# Power.net
KiCad netlist of a schematic drawn in Altium Designer
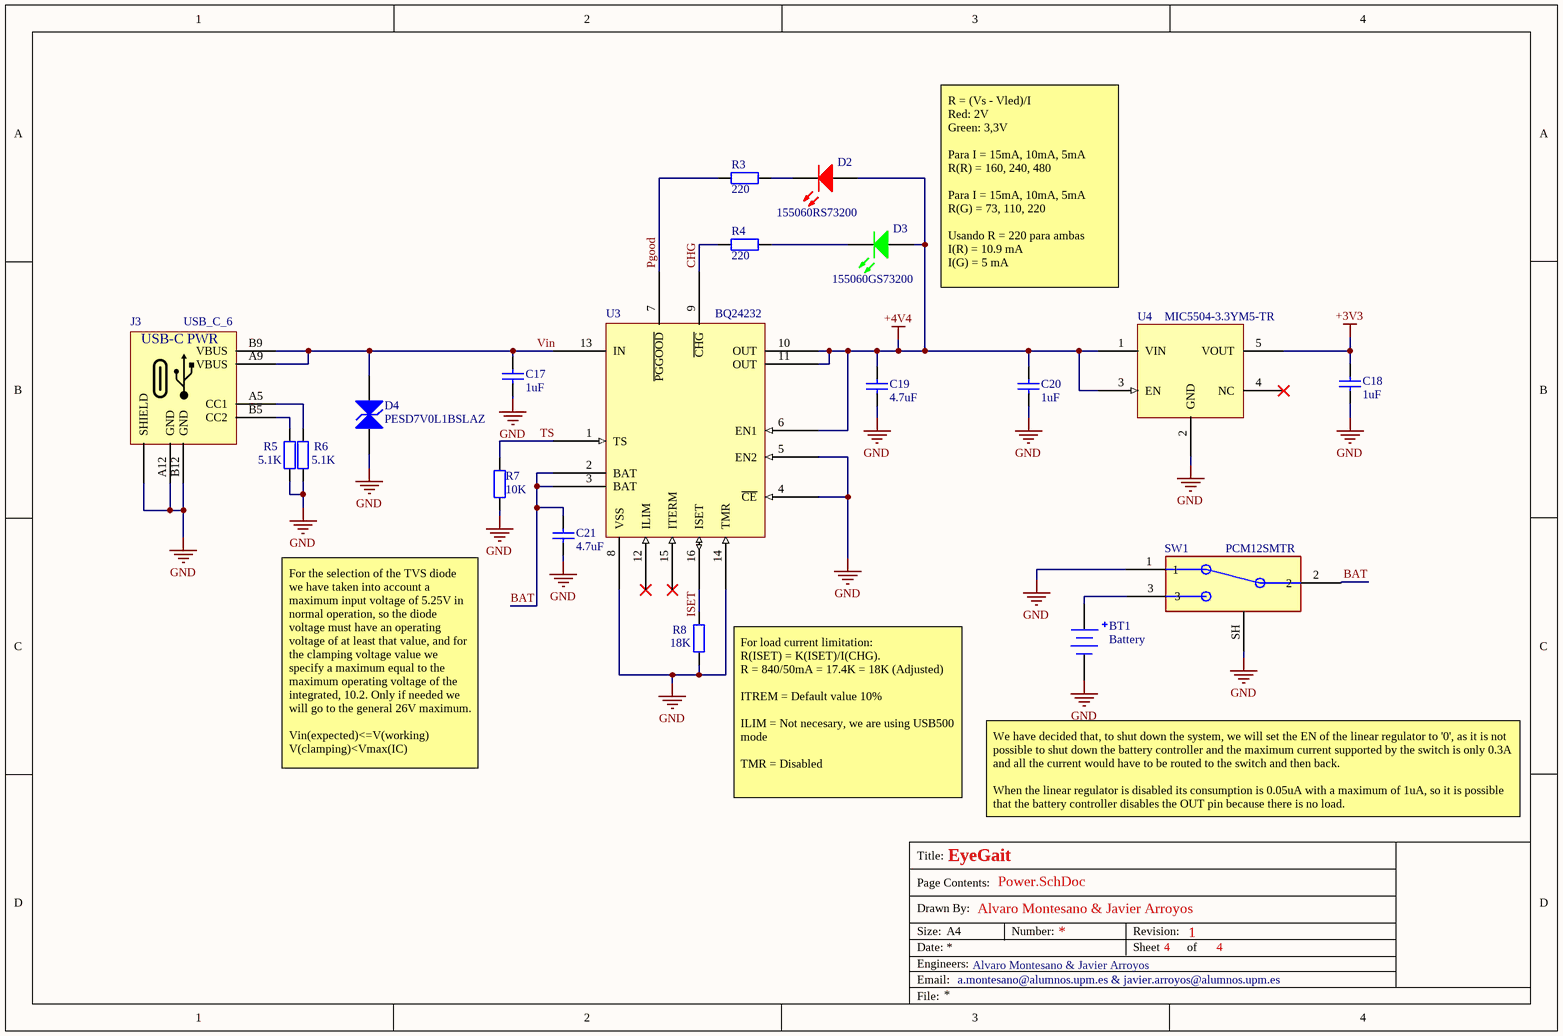
[diagram p0: Power.SchDoc]

(export (version "E")
  (design (tool "Eeschema 10.0.6"))
  (components
    (comp (ref "BT1")
      (value "Battery")
      (footprint "Hand solder wire polarity")
      (description "Multicell Battery")
      (libsource (lib "DEOP2324") (part "Battery"))
    )
    (comp (ref "C17")
      (value "1uF")
      (footprint "C0402")
      (description "Capacitor")
      (libsource (lib "DEOP2324") (part "C"))
    )
    (comp (ref "C18")
      (value "1uF")
      (footprint "C0402")
      (description "Capacitor")
      (libsource (lib "DEOP2324") (part "C"))
    )
    (comp (ref "C19")
      (value "4.7uF")
      (footprint "C0402")
      (description "Capacitor")
      (fields (field (name "VOLTAGE") ">10V"))
      (libsource (lib "DEOP2324") (part "C"))
    )
    (comp (ref "C20")
      (value "1uF")
      (footprint "C0402")
      (description "Capacitor")
      (libsource (lib "DEOP2324") (part "C"))
    )
    (comp (ref "C21")
      (value "4.7uF")
      (footprint "C0402")
      (description "Capacitor")
      (libsource (lib "DEOP2324") (part "C"))
    )
    (comp (ref "D2")
      (value "155060RS73200")
      (footprint "LED_Side_0603")
      (description "Red LED")
      (libsource (lib "DEOP2324") (part "LED_R"))
    )
    (comp (ref "D3")
      (value "155060GS73200")
      (footprint "LED_Side_0603")
      (description "Green LED")
      (libsource (lib "DEOP2324") (part "LED_G"))
    )
    (comp (ref "D4")
      (value "PESD7V0L1BSLAZ")
      (footprint "DFN1006-2/SOD882")
      (description "Zener Diode Bidirectional")
      (libsource (lib "DEOP2324") (part "D Zener_Bidirectional"))
    )
    (comp (ref "J3")
      (value "USB_C_6")
      (footprint "USB4135-GF-A")
      (description "USB-C 6 pin connector for power only. 20V/3A")
      (libsource (lib "DEOP2324") (part "USB_C_6"))
    )
    (comp (ref "R3")
      (value "220")
      (footprint "R0402")
      (description "Resistor")
      (libsource (lib "") (part "R_2"))
    )
    (comp (ref "R4")
      (value "220")
      (footprint "R0402")
      (description "Resistor")
      (libsource (lib "") (part "R_2"))
    )
    (comp (ref "R5")
      (value "5.1K")
      (footprint "R0402")
      (description "Resistor")
      (libsource (lib "DEOP2324") (part "R"))
    )
    (comp (ref "R6")
      (value "5.1K")
      (footprint "R0402")
      (description "Resistor")
      (libsource (lib "DEOP2324") (part "R"))
    )
    (comp (ref "R7")
      (value "10K")
      (footprint "R0402")
      (description "Resistor")
      (libsource (lib "") (part "R_1"))
    )
    (comp (ref "R8")
      (value "18K")
      (footprint "R0402")
      (description "Resistor")
      (libsource (lib "DEOP2324") (part "R"))
    )
    (comp (ref "SW1")
      (value "PCM12SMTR")
      (footprint "PCM12SMTR")
      (libsource (lib "DEOP2324") (part "PCM12SMTR"))
    )
    (comp (ref "U3")
      (value "BQ24232")
      (footprint "QFN50P300X300X100_HS-17N")
      (description "Power management IC. USB-Friendly Lithium-Ion Battery Charger And Power-Path Management IC")
      (libsource (lib "DEOP2324") (part "BQ24232"))
    )
    (comp (ref "U4")
      (value "MIC5504-3.3YM5-TR")
      (footprint "SOT23-5")
      (libsource (lib "DEOP2324") (part "MIC5504-3.3YM5-TR"))
    )
  )
  (nets
    (net (code "1") (name "+3V3") (class "Default")
      (node (ref "C18") (pin "1") (pinfunction "1_1") (pintype "passive"))
      (node (ref "U4") (pin "5") (pinfunction "VOUT_5") (pintype "power_in"))
    )
    (net (code "2") (name "+4V4") (class "Default")
      (node (ref "C19") (pin "1") (pinfunction "1_1") (pintype "passive"))
      (node (ref "C20") (pin "1") (pinfunction "1_1") (pintype "passive"))
      (node (ref "D2") (pin "1") (pinfunction "A_1") (pintype "passive"))
      (node (ref "D3") (pin "1") (pinfunction "A_1") (pintype "passive"))
      (node (ref "U3") (pin "10") (pinfunction "OUT_10") (pintype "power_in"))
      (node (ref "U3") (pin "11") (pinfunction "OUT_11") (pintype "power_in"))
      (node (ref "U3") (pin "6") (pinfunction "EN1_6") (pintype "input"))
      (node (ref "U4") (pin "1") (pinfunction "VIN_1") (pintype "power_in"))
      (node (ref "U4") (pin "3") (pinfunction "EN_3") (pintype "input"))
    )
    (net (code "3") (name "/BAT") (class "Default")
      (node (ref "C21") (pin "1") (pinfunction "1_1") (pintype "passive"))
      (node (ref "SW1") (pin "2") (pinfunction "2_2") (pintype "passive"))
      (node (ref "U3") (pin "2") (pinfunction "BAT_2") (pintype "power_in"))
      (node (ref "U3") (pin "3") (pinfunction "BAT_3") (pintype "power_in"))
    )
    (net (code "4") (name "/CHG") (class "Default")
      (node (ref "R4") (pin "2") (pinfunction "2_2") (pintype "passive"))
      (node (ref "U3") (pin "9") (pinfunction "~{CHG}_9") (pintype "open_collector"))
    )
    (net (code "5") (name "/ISET") (class "Default")
      (node (ref "R8") (pin "2") (pinfunction "2_2") (pintype "passive"))
      (node (ref "U3") (pin "16") (pinfunction "ISET_16") (pintype "bidirectional"))
    )
    (net (code "6") (name "/Pgood") (class "Default")
      (node (ref "R3") (pin "2") (pinfunction "2_2") (pintype "passive"))
      (node (ref "U3") (pin "7") (pinfunction "~{PGGOOD}_7") (pintype "open_collector"))
    )
    (net (code "7") (name "/TS") (class "Default")
      (node (ref "R7") (pin "1") (pinfunction "1_1") (pintype "passive"))
      (node (ref "U3") (pin "1") (pinfunction "TS_1") (pintype "input"))
    )
    (net (code "8") (name "/Vin") (class "Default")
      (node (ref "C17") (pin "1") (pinfunction "1_1") (pintype "passive"))
      (node (ref "D4") (pin "2") (pinfunction "K_2") (pintype "passive"))
      (node (ref "J3") (pin "A9") (pinfunction "VBUS_A9") (pintype "power_in"))
      (node (ref "J3") (pin "B9") (pinfunction "VBUS_B9") (pintype "power_in"))
      (node (ref "U3") (pin "13") (pinfunction "IN_13") (pintype "power_in"))
    )
    (net (code "9") (name "GND") (class "Default")
      (node (ref "BT1") (pin "2") (pinfunction "-_2") (pintype "passive"))
      (node (ref "C17") (pin "2") (pinfunction "2_2") (pintype "passive"))
      (node (ref "C18") (pin "2") (pinfunction "2_2") (pintype "passive"))
      (node (ref "C19") (pin "2") (pinfunction "2_2") (pintype "passive"))
      (node (ref "C20") (pin "2") (pinfunction "2_2") (pintype "passive"))
      (node (ref "C21") (pin "2") (pinfunction "2_2") (pintype "passive"))
      (node (ref "D4") (pin "1") (pinfunction "A_1") (pintype "passive"))
      (node (ref "J3") (pin "A12") (pinfunction "GND_A12") (pintype "power_in"))
      (node (ref "J3") (pin "B12") (pinfunction "GND_B12") (pintype "power_in"))
      (node (ref "J3") (pin "SHIELD") (pinfunction "SHIELD_SHIELD") (pintype "passive"))
      (node (ref "R5") (pin "1") (pinfunction "1_1") (pintype "passive"))
      (node (ref "R6") (pin "1") (pinfunction "1_1") (pintype "passive"))
      (node (ref "R7") (pin "2") (pinfunction "2_2") (pintype "passive"))
      (node (ref "R8") (pin "1") (pinfunction "1_1") (pintype "passive"))
      (node (ref "SW1") (pin "1") (pinfunction "1_1") (pintype "passive"))
      (node (ref "SW1") (pin "SH") (pinfunction "SH_SH") (pintype "passive"))
      (node (ref "U3") (pin "14") (pinfunction "TMR_14") (pintype "input"))
      (node (ref "U3") (pin "4") (pinfunction "~{CE}_4") (pintype "input"))
      (node (ref "U3") (pin "5") (pinfunction "EN2_5") (pintype "input"))
      (node (ref "U3") (pin "8") (pinfunction "VSS_8") (pintype "power_in"))
      (node (ref "U4") (pin "2") (pinfunction "GND_2") (pintype "power_in"))
    )
    (net (code "10") (name "Net-(BT1-+)") (class "Default")
      (node (ref "BT1") (pin "1") (pinfunction "+_1") (pintype "passive"))
      (node (ref "SW1") (pin "3") (pinfunction "3_3") (pintype "passive"))
    )
    (net (code "11") (name "Net-(D2-K)") (class "Default")
      (node (ref "D2") (pin "2") (pinfunction "K_2") (pintype "passive"))
      (node (ref "R3") (pin "1") (pinfunction "1_1") (pintype "passive"))
    )
    (net (code "12") (name "Net-(D3-K)") (class "Default")
      (node (ref "D3") (pin "2") (pinfunction "K_2") (pintype "passive"))
      (node (ref "R4") (pin "1") (pinfunction "1_1") (pintype "passive"))
    )
    (net (code "13") (name "Net-(J3-CC1)") (class "Default")
      (node (ref "J3") (pin "A5") (pinfunction "CC1_A5") (pintype "passive"))
      (node (ref "R6") (pin "2") (pinfunction "2_2") (pintype "passive"))
    )
    (net (code "14") (name "Net-(J3-CC2)") (class "Default")
      (node (ref "J3") (pin "B5") (pinfunction "CC2_B5") (pintype "passive"))
      (node (ref "R5") (pin "2") (pinfunction "2_2") (pintype "passive"))
    )
    (net (code "15") (name "unconnected-(U3-ILIM-Pad12)") (class "Default")
      (node (ref "U3") (pin "12") (pinfunction "ILIM_12") (pintype "input+no_connect"))
    )
    (net (code "16") (name "unconnected-(U3-ITERM-Pad15)") (class "Default")
      (node (ref "U3") (pin "15") (pinfunction "ITERM_15") (pintype "input+no_connect"))
    )
    (net (code "17") (name "unconnected-(U4-NC-Pad4)") (class "Default")
      (node (ref "U4") (pin "4") (pinfunction "NC_4") (pintype "passive+no_connect"))
    )
  )
)
